# TPS22917_Breakout.net
KiCad netlist of a schematic drawn in EAGLE
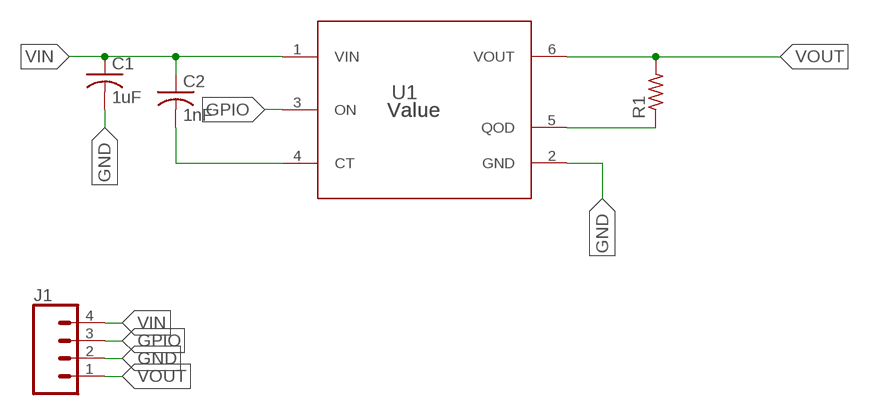
[diagram p0: schematic, sheet 1]

(export (version "E")
  (design (tool "Eeschema 10.0.6"))
  (components
    (comp (ref "C1")
      (value "1uF")
      (footprint "eagle-import:C0603")
      (libsource (lib "eagle-import") (part "C-USC0603"))
    )
    (comp (ref "C2")
      (value "1nF")
      (footprint "eagle-import:C0603")
      (libsource (lib "eagle-import") (part "C-USC0603"))
    )
    (comp (ref "J1")
      (value "CONN_041X04_NO_SILK")
      (footprint "eagle-import:1X04_NO_SILK")
      (libsource (lib "eagle-import") (part "CONN_041X04_NO_SILK"))
    )
    (comp (ref "R1")
      (value "R-US_R0603")
      (footprint "eagle-import:R0603")
      (libsource (lib "eagle-import") (part "R-US_R0603"))
    )
    (comp (ref "U1")
      (value "Value")
      (footprint "eagle-import:DBV0006_L")
      (fields (field (name "MANUFACTURER") "Texas Instruments") (field (name "PARTNUMBER") "TPS22917DBVR"))
      (libsource (lib "eagle-import") (part "TPS22917DBVRDBV0006_L"))
    )
  )
  (nets
    (net (code "1") (name "GND") (class "Default")
      (node (ref "C1") (pin "2") (pinfunction "2_2") (pintype "passive"))
      (node (ref "J1") (pin "2") (pinfunction "2_2") (pintype "passive"))
      (node (ref "U1") (pin "2") (pinfunction "GND_2") (pintype "power_in"))
    )
    (net (code "2") (name "GPIO") (class "Default")
      (node (ref "J1") (pin "3") (pinfunction "3_3") (pintype "passive"))
      (node (ref "U1") (pin "3") (pinfunction "ON_3") (pintype "input"))
    )
    (net (code "3") (name "Net-(U1-CT)") (class "Default")
      (node (ref "C2") (pin "2") (pinfunction "2_2") (pintype "passive"))
      (node (ref "U1") (pin "4") (pinfunction "CT_4") (pintype "output"))
    )
    (net (code "4") (name "Net-(U1-QOD)") (class "Default")
      (node (ref "R1") (pin "1") (pinfunction "1_1") (pintype "passive"))
      (node (ref "U1") (pin "5") (pinfunction "QOD_5") (pintype "input"))
    )
    (net (code "5") (name "VIN") (class "Default")
      (node (ref "C1") (pin "1") (pinfunction "1_1") (pintype "passive"))
      (node (ref "C2") (pin "1") (pinfunction "1_1") (pintype "passive"))
      (node (ref "J1") (pin "4") (pinfunction "4_4") (pintype "passive"))
      (node (ref "U1") (pin "1") (pinfunction "VIN_1") (pintype "power_in"))
    )
    (net (code "6") (name "VOUT") (class "Default")
      (node (ref "J1") (pin "1") (pinfunction "1_1") (pintype "passive"))
      (node (ref "R1") (pin "2") (pinfunction "2_2") (pintype "passive"))
      (node (ref "U1") (pin "6") (pinfunction "VOUT_6") (pintype "power_in"))
    )
  )
)
